# S3_LED_MAT_FPGA.net
KiCad netlist of a schematic drawn in Altium Designer
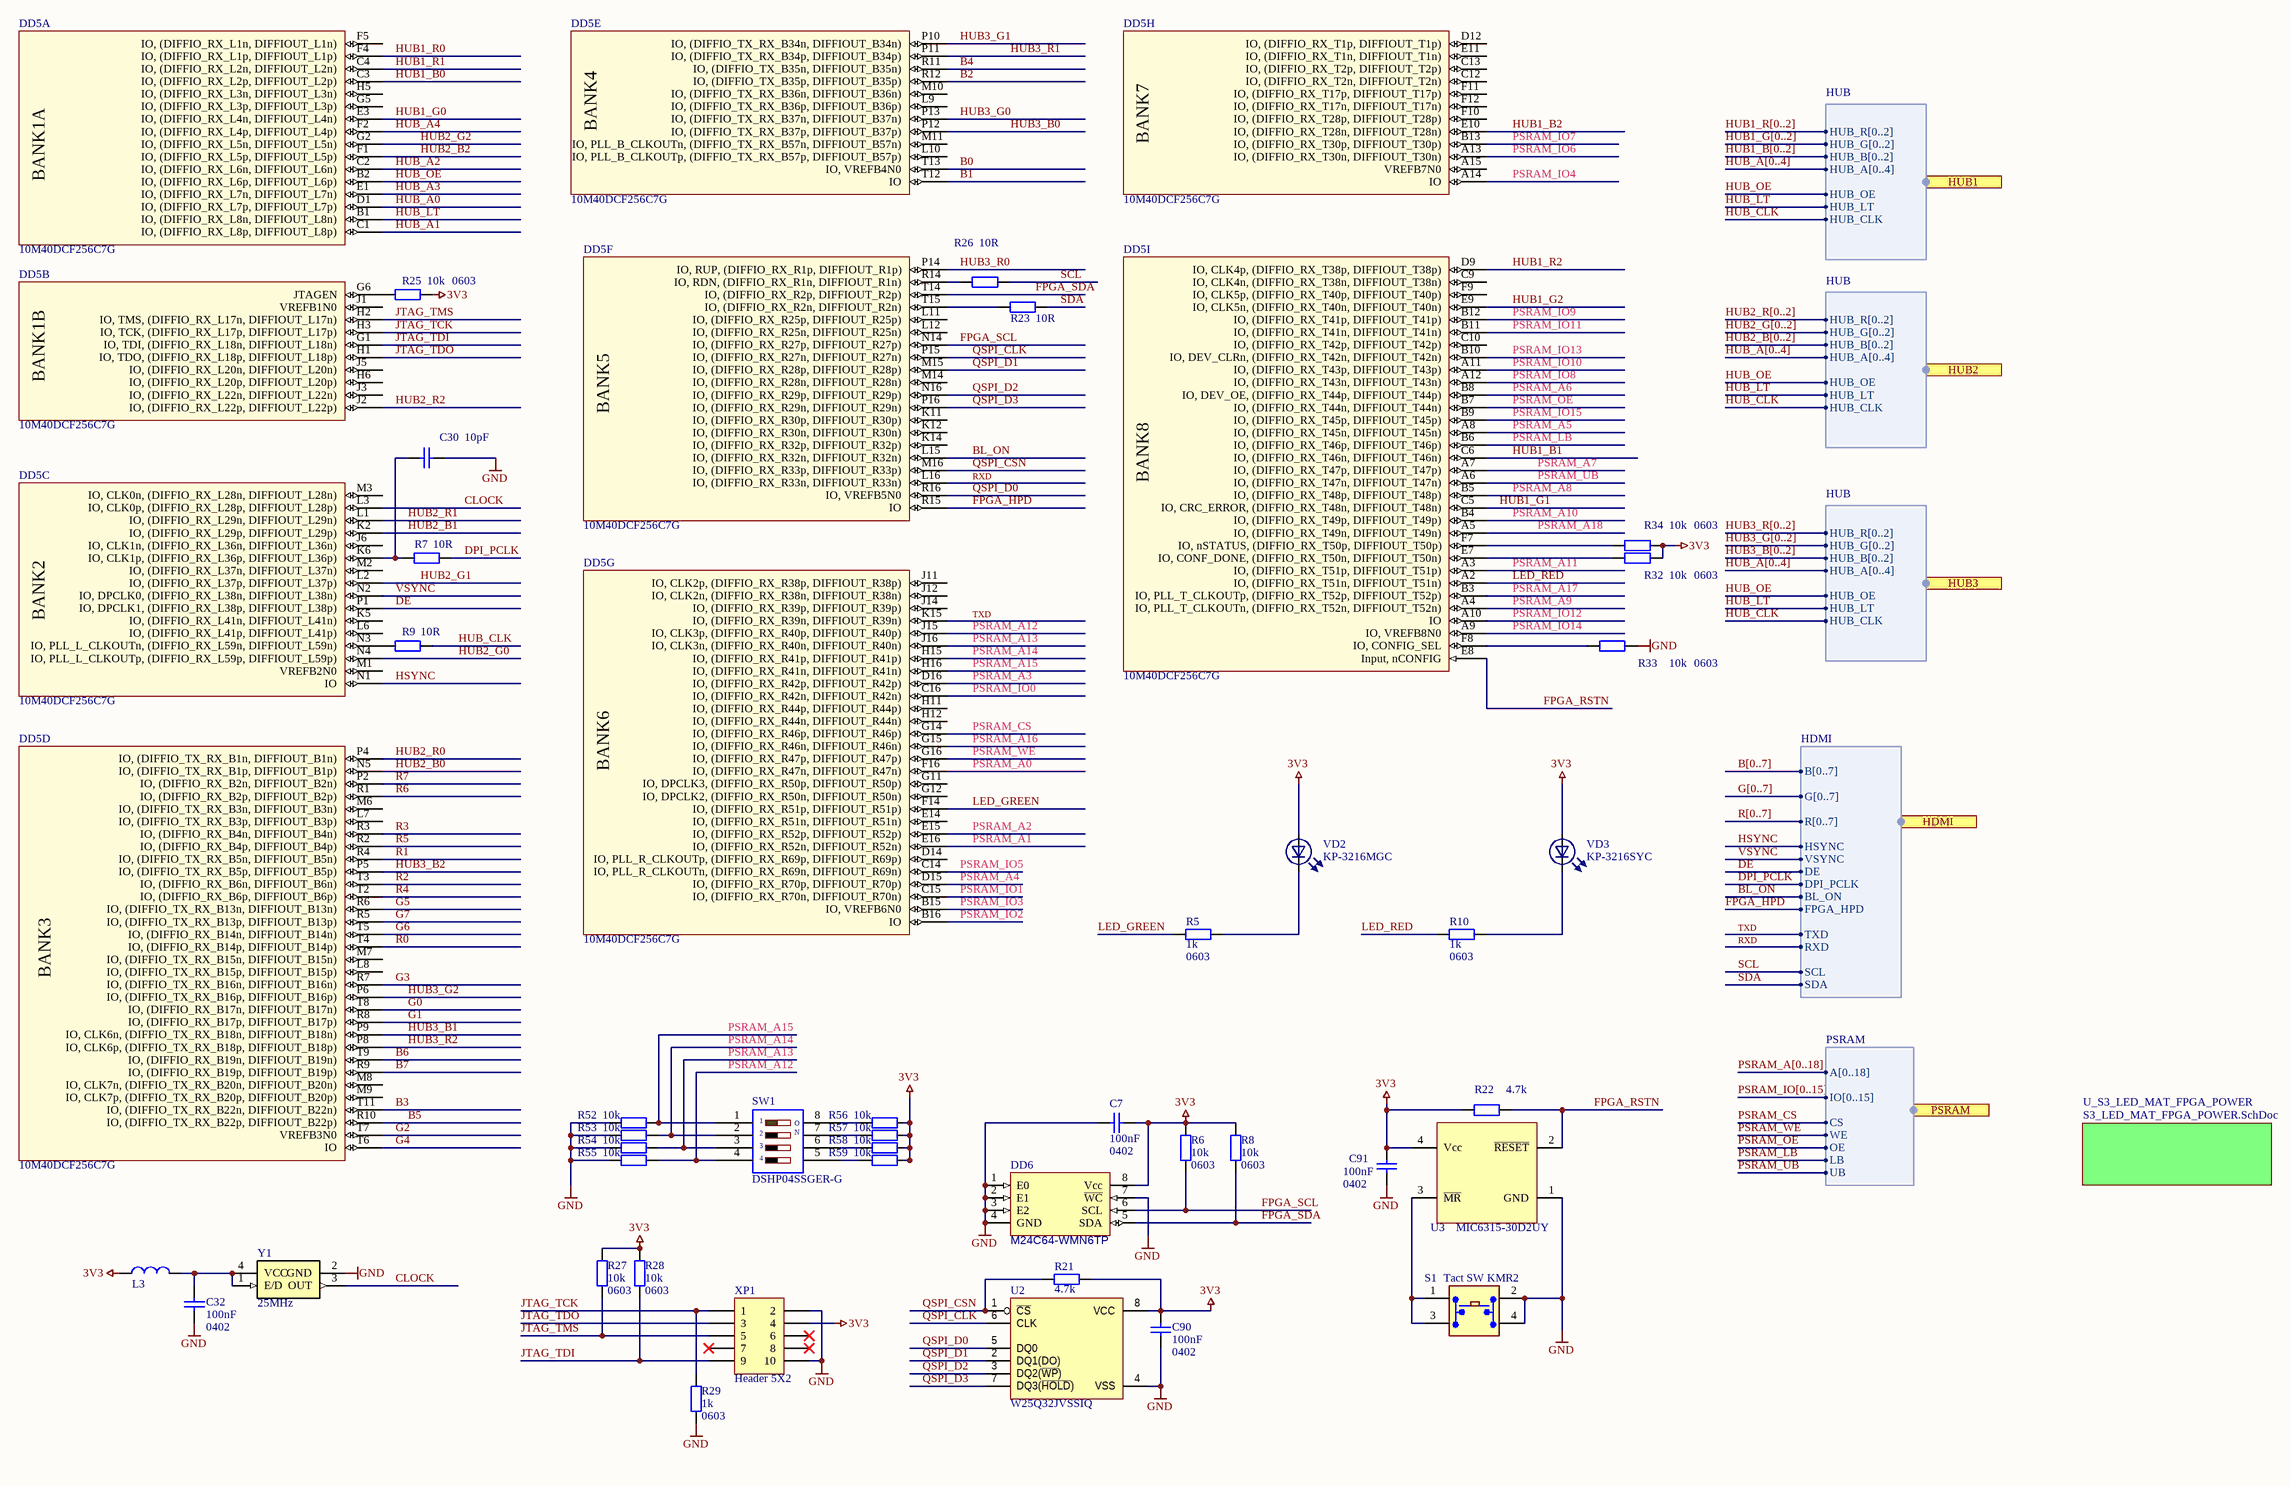
[diagram p0: S3_LED_MAT_FPGA.SCHDOC]

(export (version "E")
  (design (tool "Eeschema 10.0.6"))
  (components
    (comp (ref "C7")
      (value "100nF")
      (footprint "CAPC1005L")
      (description "Capacitor ceramic")
      (fields
        (field (name "MANUFACTURER") "SAMSUNG")
        (field (name "MANUFACTURER PART NUMBER") "CL05B104KO5NNNC")
        (field (name "PACKAGE") "0402")
      )
      (libsource (lib "LED_MAT_3") (part "100nF / 0402 / X7R / 16V"))
    )
    (comp (ref "C30")
      (value "10pF")
      (footprint "CAPC1608L")
      (description "Capacitor ceramic")
      (fields
        (field (name "MANUFACTURER") "SAMSUNG")
        (field (name "MANUFACTURER PART NUMBER") "CL10C100JB8NNNC")
      )
      (libsource (lib "LED_MAT_3") (part "10pF / 0603 / COG / 50V"))
    )
    (comp (ref "C32")
      (value "100nF")
      (footprint "CAPC1005L")
      (description "Capacitor ceramic")
      (fields
        (field (name "MANUFACTURER") "SAMSUNG")
        (field (name "MANUFACTURER PART NUMBER") "CL05B104KO5NNNC")
        (field (name "PACKAGE") "0402")
      )
      (libsource (lib "LED_MAT_3") (part "100nF / 0402 / X7R / 16V"))
    )
    (comp (ref "C90")
      (value "100nF")
      (footprint "CAPC1005L")
      (description "Capacitor ceramic")
      (fields
        (field (name "MANUFACTURER") "SAMSUNG")
        (field (name "MANUFACTURER PART NUMBER") "CL05B104KO5NNNC")
        (field (name "PACKAGE") "0402")
      )
      (libsource (lib "LED_MAT_3") (part "100nF / 0402 / X7R / 16V"))
    )
    (comp (ref "C91")
      (value "100nF")
      (footprint "CAPC1005L")
      (description "Capacitor ceramic")
      (fields
        (field (name "MANUFACTURER") "SAMSUNG")
        (field (name "MANUFACTURER PART NUMBER") "CL05B104KO5NNNC")
        (field (name "PACKAGE") "0402")
      )
      (libsource (lib "LED_MAT_3") (part "100nF / 0402 / X7R / 16V"))
    )
    (comp (ref "DD5")
      (value "10M40DCF256C7G")
      (footprint "BGA100P16X16-256")
      (description "FPGA")
      (fields
        (field (name "MANUFACTURER") "ALTERA")
        (field (name "MANUFACTURER PART NUMBER") "10M40DCF256C7GA")
      )
      (libsource (lib "IC") (part "10M40DCF256C7G"))
    )
    (comp (ref "DD6")
      (value "M24C64-WMN6TP")
      (footprint "SOIC127P600-8N")
      (fields
        (field (name "MANUFACTURER") "ST")
        (field (name "TOLERANCE") "./.")
        (field (name "VOLTAGE") "3.0...5.5V")
      )
      (libsource (lib "LED_MAT_3") (part "M24C64-WDW6TP"))
    )
    (comp (ref "L3")
      (value "~")
      (footprint "INDC1005L")
      (description "General 0402 - type Chip Inductor")
      (fields
        (field (name "MANUFACTURER") "Murata")
        (field (name "MANUFACTURER PART NUMBER") "BLM15AG601SN1")
      )
      (libsource (lib "LED_MAT_3") (part "L0402_BLM15"))
    )
    (comp (ref "R5")
      (value "1k")
      (footprint "RESC1608L")
      (description "Resistor")
      (fields (field (name "TOLERANCE") "1%") (field (name "PACKAGE") "0603") (field (name "VOLTAGE") "50V"))
      (libsource (lib "LED_MAT_3") (part "1k / 1% / 0603 / TC100 / 50V / 0.1W"))
    )
    (comp (ref "R6")
      (value "10k")
      (footprint "RESC1608L")
      (description "Resistor")
      (fields (field (name "TOLERANCE") "1%") (field (name "PACKAGE") "0603") (field (name "VOLTAGE") "50V"))
      (libsource (lib "") (part "10k / 1% / 0603 / TC100 / 50V / 0.1W_2"))
    )
    (comp (ref "R7")
      (value "10R")
      (footprint "RESC1608L")
      (description "10R / 1% / 0603")
      (fields
        (field (name "MANUFACTURER") "YAGEO")
        (field (name "MANUFACTURER PART NUMBER") "RC0603FR-0710RL")
      )
      (libsource (lib "LED_MAT_3") (part "10R / 1% / 0603"))
    )
    (comp (ref "R8")
      (value "10k")
      (footprint "RESC1608L")
      (description "Resistor")
      (fields (field (name "TOLERANCE") "1%") (field (name "PACKAGE") "0603") (field (name "VOLTAGE") "50V"))
      (libsource (lib "") (part "10k / 1% / 0603 / TC100 / 50V / 0.1W_1"))
    )
    (comp (ref "R9")
      (value "10R")
      (footprint "RESC1608L")
      (description "10R / 1% / 0603")
      (fields
        (field (name "MANUFACTURER") "YAGEO")
        (field (name "MANUFACTURER PART NUMBER") "RC0603FR-0710RL")
      )
      (libsource (lib "LED_MAT_3") (part "10R / 1% / 0603"))
    )
    (comp (ref "R10")
      (value "1k")
      (footprint "RESC1608L")
      (description "Resistor")
      (fields (field (name "TOLERANCE") "1%") (field (name "PACKAGE") "0603") (field (name "VOLTAGE") "50V"))
      (libsource (lib "LED_MAT_3") (part "1k / 1% / 0603 / TC100 / 50V / 0.1W"))
    )
    (comp (ref "R21")
      (value "4.7k")
      (footprint "RESC1608L")
      (description "4.7k / 1% / 0603")
      (fields
        (field (name "MANUFACTURER") "YAGEO")
        (field (name "MANUFACTURER PART NUMBER") "RC0603FR-074K7L")
      )
      (libsource (lib "LED_MAT_3") (part "4.7k / 1% / 0603"))
    )
    (comp (ref "R22")
      (value "4.7k")
      (footprint "RESC1608L")
      (description "4.7k / 1% / 0603")
      (fields
        (field (name "MANUFACTURER") "YAGEO")
        (field (name "MANUFACTURER PART NUMBER") "RC0603FR-074K7L")
      )
      (libsource (lib "LED_MAT_3") (part "4.7k / 1% / 0603"))
    )
    (comp (ref "R23")
      (value "10R")
      (footprint "RESC1608L")
      (description "10R / 1% / 0603")
      (fields
        (field (name "MANUFACTURER") "YAGEO")
        (field (name "MANUFACTURER PART NUMBER") "RC0603FR-0710RL")
      )
      (libsource (lib "LED_MAT_3") (part "10R / 1% / 0603"))
    )
    (comp (ref "R25")
      (value "10k")
      (footprint "RESC1608L")
      (description "Resistor")
      (fields (field (name "TOLERANCE") "1%") (field (name "PACKAGE") "0603") (field (name "VOLTAGE") "50V"))
      (libsource (lib "LED_MAT_3") (part "10k / 1% / 0603 / TC100 / 50V / 0.1W"))
    )
    (comp (ref "R26")
      (value "10R")
      (footprint "RESC1608L")
      (description "10R / 1% / 0603")
      (fields
        (field (name "MANUFACTURER") "YAGEO")
        (field (name "MANUFACTURER PART NUMBER") "RC0603FR-0710RL")
      )
      (libsource (lib "LED_MAT_3") (part "10R / 1% / 0603"))
    )
    (comp (ref "R27")
      (value "10k")
      (footprint "RESC1608L")
      (description "Resistor")
      (fields (field (name "TOLERANCE") "1%") (field (name "PACKAGE") "0603") (field (name "VOLTAGE") "50V"))
      (libsource (lib "") (part "10k / 1% / 0603 / TC100 / 50V / 0.1W_1"))
    )
    (comp (ref "R28")
      (value "10k")
      (footprint "RESC1608L")
      (description "Resistor")
      (fields (field (name "TOLERANCE") "1%") (field (name "PACKAGE") "0603") (field (name "VOLTAGE") "50V"))
      (libsource (lib "") (part "10k / 1% / 0603 / TC100 / 50V / 0.1W_1"))
    )
    (comp (ref "R29")
      (value "1k")
      (footprint "RESC1608L")
      (description "Resistor")
      (fields (field (name "TOLERANCE") "1%") (field (name "PACKAGE") "0603") (field (name "VOLTAGE") "50V"))
      (libsource (lib "") (part "1k / 1% / 0603 / TC100 / 50V / 0.1W_1"))
    )
    (comp (ref "R32")
      (value "10k")
      (footprint "RESC1608L")
      (description "Resistor")
      (fields (field (name "TOLERANCE") "1%") (field (name "PACKAGE") "0603") (field (name "VOLTAGE") "50V"))
      (libsource (lib "LED_MAT_3") (part "10k / 1% / 0603 / TC100 / 50V / 0.1W"))
    )
    (comp (ref "R33")
      (value "10k")
      (footprint "RESC1608L")
      (description "Resistor")
      (fields (field (name "TOLERANCE") "1%") (field (name "PACKAGE") "0603") (field (name "VOLTAGE") "50V"))
      (libsource (lib "LED_MAT_3") (part "10k / 1% / 0603 / TC100 / 50V / 0.1W"))
    )
    (comp (ref "R34")
      (value "10k")
      (footprint "RESC1608L")
      (description "Resistor")
      (fields (field (name "TOLERANCE") "1%") (field (name "PACKAGE") "0603") (field (name "VOLTAGE") "50V"))
      (libsource (lib "LED_MAT_3") (part "10k / 1% / 0603 / TC100 / 50V / 0.1W"))
    )
    (comp (ref "R52")
      (value "10k")
      (footprint "RESC1608L")
      (description "Resistor")
      (fields (field (name "TOLERANCE") "1%") (field (name "VOLTAGE") "50V"))
      (libsource (lib "LED_MAT_3") (part "10k / 1% / 0603 / TC100 / 50V / 0.1W"))
    )
    (comp (ref "R53")
      (value "10k")
      (footprint "RESC1608L")
      (description "Resistor")
      (fields (field (name "TOLERANCE") "1%") (field (name "VOLTAGE") "50V"))
      (libsource (lib "LED_MAT_3") (part "10k / 1% / 0603 / TC100 / 50V / 0.1W"))
    )
    (comp (ref "R54")
      (value "10k")
      (footprint "RESC1608L")
      (description "Resistor")
      (fields (field (name "TOLERANCE") "1%") (field (name "VOLTAGE") "50V"))
      (libsource (lib "LED_MAT_3") (part "10k / 1% / 0603 / TC100 / 50V / 0.1W"))
    )
    (comp (ref "R55")
      (value "10k")
      (footprint "RESC1608L")
      (description "Resistor")
      (fields (field (name "TOLERANCE") "1%") (field (name "VOLTAGE") "50V"))
      (libsource (lib "LED_MAT_3") (part "10k / 1% / 0603 / TC100 / 50V / 0.1W"))
    )
    (comp (ref "R56")
      (value "10k")
      (footprint "RESC1608L")
      (description "Resistor")
      (fields (field (name "TOLERANCE") "1%") (field (name "VOLTAGE") "50V"))
      (libsource (lib "LED_MAT_3") (part "10k / 1% / 0603 / TC100 / 50V / 0.1W"))
    )
    (comp (ref "R57")
      (value "10k")
      (footprint "RESC1608L")
      (description "Resistor")
      (fields (field (name "TOLERANCE") "1%") (field (name "VOLTAGE") "50V"))
      (libsource (lib "LED_MAT_3") (part "10k / 1% / 0603 / TC100 / 50V / 0.1W"))
    )
    (comp (ref "R58")
      (value "10k")
      (footprint "RESC1608L")
      (description "Resistor")
      (fields (field (name "TOLERANCE") "1%") (field (name "VOLTAGE") "50V"))
      (libsource (lib "LED_MAT_3") (part "10k / 1% / 0603 / TC100 / 50V / 0.1W"))
    )
    (comp (ref "R59")
      (value "10k")
      (footprint "RESC1608L")
      (description "Resistor")
      (fields (field (name "TOLERANCE") "1%") (field (name "VOLTAGE") "50V"))
      (libsource (lib "LED_MAT_3") (part "10k / 1% / 0603 / TC100 / 50V / 0.1W"))
    )
    (comp (ref "S1")
      (value "Tact SW KMR2")
      (footprint "SW4SMD_63X161LS")
      (description "Microminiature Tact Switch for SMT")
      (fields
        (field (name "MANUFACTURER") "C&K Components")
        (field (name "MANUFACTURER PART NUMBER") "KMR211GLFS")
      )
      (libsource (lib "LED_MAT_3") (part "Tact SW KMR2"))
    )
    (comp (ref "SW1")
      (value "DSHP04SSGER-G")
      (footprint "Dipswitch 4 SO8 a")
      (description "DIP SW 4pol, 1.27mm")
      (fields (field (name "MANUFACTURER") "SWITRONIC") (field (name "TOLERANCE") "1%"))
      (libsource (lib "LED_MAT_3") (part "DIP SW 4pol, 1.27mm"))
    )
    (comp (ref "U2")
      (value "W25Q32JVSSIQ")
      (footprint "SOIC127P800X216-8L")
      (description "32Mbit Quad Serial Flash in SOIC W package")
      (fields (field (name "MANUFACTURER") "WINBOND") (field (name "TOLERANCE") "./."))
      (libsource (lib "LED_MAT_3") (part "W25Q32JVSSIQ"))
    )
    (comp (ref "U3")
      (value "MIC6315-30D2UY")
      (footprint "SOT-143")
      (description "3V VOLTAGE SUPERVISOR")
      (fields (field (name "MANUFACTURER") "MICROCHIP") (field (name "VOLTAGE") "3.3V"))
      (libsource (lib "LED_MAT_3") (part "MIC6315"))
    )
    (comp (ref "VD2")
      (value "KP-3216MGC")
      (footprint "LED3216X10L")
      (description "SMD LED GREEN")
      (fields (field (name "MANUFACTURER") "KINGBRIGHT"))
      (libsource (lib "LED_MAT_3") (part "KP-3216MGC"))
    )
    (comp (ref "VD3")
      (value "KP-3216SYC")
      (footprint "LED3216X10L")
      (description "SMD LED YELLOW")
      (fields (field (name "MANUFACTURER") "KINGBRIGHT"))
      (libsource (lib "LED_MAT_3") (part "KP-3216SYC"))
    )
    (comp (ref "XP1")
      (value "Header 5X2")
      (footprint "PLD10")
      (description "Header, 5-Pin, Dual row")
      (fields (field (name "MANUFACTURER") "FCI") (field (name "VOLTAGE") "50V"))
      (libsource (lib "LED_MAT_3") (part "Header 5X2"))
    )
    (comp (ref "Y1")
      (value "25MHz")
      (footprint "SMD03025/4CC")
      (description "SMD Oscillator with Stop Function")
      (fields
        (field (name "MANUFACTURER") "YOKETANT")
        (field (name "MANUFACTURER PART NUMBER") "SO3225-025000-FIE-BBA-A1")
      )
      (libsource (lib "LED_MAT_3") (part "OSC / 3225 / 25M"))
    )
  )
  (nets
    (net (code "6") (name "/B0") (class "Default")
      (node (ref "DD5") (pin "T13") (pinfunction "IO,_VREFB4N0_T13") (pintype "bidirectional"))
    )
    (net (code "7") (name "/B1") (class "Default")
      (node (ref "DD5") (pin "T12") (pinfunction "IO_T12") (pintype "bidirectional"))
    )
    (net (code "8") (name "/B2") (class "Default")
      (node (ref "DD5") (pin "R12") (pinfunction "IO,_(DIFFIO_TX_B35p,_DIFFIOUT_B35p)_R12") (pintype "bidirectional"))
    )
    (net (code "9") (name "/B3") (class "Default")
      (node (ref "DD5") (pin "T11") (pinfunction "IO,_(DIFFIO_TX_RX_B22n,_DIFFIOUT_B22n)_T11") (pintype "bidirectional"))
    )
    (net (code "10") (name "/B4") (class "Default")
      (node (ref "DD5") (pin "R11") (pinfunction "IO,_(DIFFIO_TX_B35n,_DIFFIOUT_B35n)_R11") (pintype "bidirectional"))
    )
    (net (code "11") (name "/B5") (class "Default")
      (node (ref "DD5") (pin "R10") (pinfunction "IO,_(DIFFIO_TX_RX_B22p,_DIFFIOUT_B22p)_R10") (pintype "bidirectional"))
    )
    (net (code "12") (name "/B6") (class "Default")
      (node (ref "DD5") (pin "T9") (pinfunction "IO,_(DIFFIO_RX_B19n,_DIFFIOUT_B19n)_T9") (pintype "bidirectional"))
    )
    (net (code "13") (name "/B7") (class "Default")
      (node (ref "DD5") (pin "R9") (pinfunction "IO,_(DIFFIO_RX_B19p,_DIFFIOUT_B19p)_R9") (pintype "bidirectional"))
    )
    (net (code "14") (name "/BL_ON") (class "Default")
      (node (ref "DD5") (pin "L15") (pinfunction "IO,_(DIFFIO_RX_R32n,_DIFFIOUT_R32n)_L15") (pintype "bidirectional"))
    )
    (net (code "16") (name "/CLOCK") (class "Default")
      (node (ref "DD5") (pin "L3") (pinfunction "IO,_CLK0p,_(DIFFIO_RX_L28p,_DIFFIOUT_L28p)_L3") (pintype "bidirectional"))
      (node (ref "Y1") (pin "3") (pinfunction "OUT_3") (pintype "output"))
    )
    (net (code "17") (name "/DE") (class "Default")
      (node (ref "DD5") (pin "P1") (pinfunction "IO,_DPCLK1,_(DIFFIO_RX_L38p,_DIFFIOUT_L38p)_P1") (pintype "bidirectional"))
    )
    (net (code "18") (name "/DPI_PCLK") (class "Default")
      (node (ref "R7") (pin "1") (pinfunction "1_1") (pintype "passive"))
    )
    (net (code "19") (name "/FPGA_HPD") (class "Default")
      (node (ref "DD5") (pin "R15") (pinfunction "IO_R15") (pintype "bidirectional"))
    )
    (net (code "20") (name "/FPGA_RSTN") (class "Default")
      (node (ref "DD5") (pin "E8") (pinfunction "Input,_nCONFIG_E8") (pintype "input"))
      (node (ref "R22") (pin "2") (pinfunction "2_2") (pintype "passive"))
      (node (ref "U3") (pin "2") (pinfunction "~{RESET}_2") (pintype "passive"))
    )
    (net (code "21") (name "/FPGA_SCL") (class "Default")
      (node (ref "DD5") (pin "N14") (pinfunction "IO,_(DIFFIO_RX_R27p,_DIFFIOUT_R27p)_N14") (pintype "bidirectional"))
      (node (ref "DD6") (pin "6") (pinfunction "SCL_6") (pintype "input"))
      (node (ref "R6") (pin "1") (pinfunction "1_1") (pintype "passive"))
    )
    (net (code "22") (name "/FPGA_SDA") (class "Default")
      (node (ref "DD5") (pin "T14") (pinfunction "IO,_(DIFFIO_RX_R2p,_DIFFIOUT_R2p)_T14") (pintype "bidirectional"))
      (node (ref "DD6") (pin "5") (pinfunction "SDA_5") (pintype "bidirectional"))
      (node (ref "R8") (pin "2") (pinfunction "2_2") (pintype "passive"))
    )
    (net (code "23") (name "/G0") (class "Default")
      (node (ref "DD5") (pin "T8") (pinfunction "IO,_(DIFFIO_RX_B17n,_DIFFIOUT_B17n)_T8") (pintype "bidirectional"))
    )
    (net (code "24") (name "/G1") (class "Default")
      (node (ref "DD5") (pin "R8") (pinfunction "IO,_(DIFFIO_RX_B17p,_DIFFIOUT_B17p)_R8") (pintype "bidirectional"))
    )
    (net (code "25") (name "/G2") (class "Default")
      (node (ref "DD5") (pin "T7") (pinfunction "VREFB3N0_T7") (pintype "bidirectional"))
    )
    (net (code "26") (name "/G3") (class "Default")
      (node (ref "DD5") (pin "R7") (pinfunction "IO,_(DIFFIO_TX_RX_B16n,_DIFFIOUT_B16n)_R7") (pintype "bidirectional"))
    )
    (net (code "27") (name "/G4") (class "Default")
      (node (ref "DD5") (pin "T6") (pinfunction "IO_T6") (pintype "bidirectional"))
    )
    (net (code "28") (name "/G5") (class "Default")
      (node (ref "DD5") (pin "R6") (pinfunction "IO,_(DIFFIO_TX_RX_B13n,_DIFFIOUT_B13n)_R6") (pintype "bidirectional"))
    )
    (net (code "29") (name "/G6") (class "Default")
      (node (ref "DD5") (pin "T5") (pinfunction "IO,_(DIFFIO_RX_B14n,_DIFFIOUT_B14n)_T5") (pintype "bidirectional"))
    )
    (net (code "30") (name "/G7") (class "Default")
      (node (ref "DD5") (pin "R5") (pinfunction "IO,_(DIFFIO_TX_RX_B13p,_DIFFIOUT_B13p)_R5") (pintype "bidirectional"))
    )
    (net (code "33") (name "/HSYNC") (class "Default")
      (node (ref "DD5") (pin "N1") (pinfunction "IO_N1") (pintype "bidirectional"))
    )
    (net (code "34") (name "/HUB1_B0") (class "Default")
      (node (ref "DD5") (pin "C3") (pinfunction "IO,_(DIFFIO_RX_L2p,_DIFFIOUT_L2p)_C3") (pintype "bidirectional"))
    )
    (net (code "35") (name "/HUB1_B1") (class "Default")
      (node (ref "DD5") (pin "C6") (pinfunction "IO,_(DIFFIO_RX_T46n,_DIFFIOUT_T46n)_C6") (pintype "bidirectional"))
    )
    (net (code "36") (name "/HUB1_B2") (class "Default")
      (node (ref "DD5") (pin "E10") (pinfunction "IO,_(DIFFIO_RX_T28n,_DIFFIOUT_T28n)_E10") (pintype "bidirectional"))
    )
    (net (code "38") (name "/HUB1_G0") (class "Default")
      (node (ref "DD5") (pin "E3") (pinfunction "IO,_(DIFFIO_RX_L4n,_DIFFIOUT_L4n)_E3") (pintype "bidirectional"))
    )
    (net (code "39") (name "/HUB1_G1") (class "Default")
      (node (ref "DD5") (pin "C5") (pinfunction "IO,_CRC_ERROR,_(DIFFIO_RX_T48n,_DIFFIOUT_T48n)_C5") (pintype "bidirectional"))
    )
    (net (code "40") (name "/HUB1_G2") (class "Default")
      (node (ref "DD5") (pin "E9") (pinfunction "IO,_CLK5n,_(DIFFIO_RX_T40n,_DIFFIOUT_T40n)_E9") (pintype "bidirectional"))
    )
    (net (code "42") (name "/HUB1_R0") (class "Default")
      (node (ref "DD5") (pin "F4") (pinfunction "IO,_(DIFFIO_RX_L1p,_DIFFIOUT_L1p)_F4") (pintype "bidirectional"))
    )
    (net (code "43") (name "/HUB1_R1") (class "Default")
      (node (ref "DD5") (pin "C4") (pinfunction "IO,_(DIFFIO_RX_L2n,_DIFFIOUT_L2n)_C4") (pintype "bidirectional"))
    )
    (net (code "44") (name "/HUB1_R2") (class "Default")
      (node (ref "DD5") (pin "D9") (pinfunction "IO,_CLK4p,_(DIFFIO_RX_T38p,_DIFFIOUT_T38p)_D9") (pintype "bidirectional"))
    )
    (net (code "47") (name "/HUB2_B0") (class "Default")
      (node (ref "DD5") (pin "N5") (pinfunction "IO,_(DIFFIO_TX_RX_B1p,_DIFFIOUT_B1p)_N5") (pintype "bidirectional"))
    )
    (net (code "48") (name "/HUB2_B1") (class "Default")
      (node (ref "DD5") (pin "K2") (pinfunction "IO,_(DIFFIO_RX_L29p,_DIFFIOUT_L29p)_K2") (pintype "bidirectional"))
    )
    (net (code "49") (name "/HUB2_B2") (class "Default")
      (node (ref "DD5") (pin "F1") (pinfunction "IO,_(DIFFIO_RX_L5p,_DIFFIOUT_L5p)_F1") (pintype "bidirectional"))
    )
    (net (code "50") (name "/HUB2_G0") (class "Default")
      (node (ref "DD5") (pin "N4") (pinfunction "IO,_PLL_L_CLKOUTp,_(DIFFIO_RX_L59p,_DIFFIOUT_L59p)_N4") (pintype "bidirectional"))
    )
    (net (code "51") (name "/HUB2_G1") (class "Default")
      (node (ref "DD5") (pin "L2") (pinfunction "IO,_(DIFFIO_RX_L37p,_DIFFIOUT_L37p)_L2") (pintype "bidirectional"))
    )
    (net (code "52") (name "/HUB2_G2") (class "Default")
      (node (ref "DD5") (pin "G2") (pinfunction "IO,_(DIFFIO_RX_L5n,_DIFFIOUT_L5n)_G2") (pintype "bidirectional"))
    )
    (net (code "54") (name "/HUB2_R0") (class "Default")
      (node (ref "DD5") (pin "P4") (pinfunction "IO,_(DIFFIO_TX_RX_B1n,_DIFFIOUT_B1n)_P4") (pintype "bidirectional"))
    )
    (net (code "55") (name "/HUB2_R1") (class "Default")
      (node (ref "DD5") (pin "L1") (pinfunction "IO,_(DIFFIO_RX_L29n,_DIFFIOUT_L29n)_L1") (pintype "bidirectional"))
    )
    (net (code "56") (name "/HUB2_R2") (class "Default")
      (node (ref "DD5") (pin "J2") (pinfunction "IO,_(DIFFIO_RX_L22p,_DIFFIOUT_L22p)_J2") (pintype "bidirectional"))
    )
    (net (code "59") (name "/HUB3_B0") (class "Default")
      (node (ref "DD5") (pin "P12") (pinfunction "IO,_(DIFFIO_TX_RX_B37p,_DIFFIOUT_B37p)_P12") (pintype "bidirectional"))
    )
    (net (code "60") (name "/HUB3_B1") (class "Default")
      (node (ref "DD5") (pin "P9") (pinfunction "IO,_CLK6n,_(DIFFIO_TX_RX_B18n,_DIFFIOUT_B18n)_P9") (pintype "bidirectional"))
    )
    (net (code "61") (name "/HUB3_B2") (class "Default")
      (node (ref "DD5") (pin "P5") (pinfunction "IO,_(DIFFIO_TX_RX_B5p,_DIFFIOUT_B5p)_P5") (pintype "bidirectional"))
    )
    (net (code "63") (name "/HUB3_G0") (class "Default")
      (node (ref "DD5") (pin "P13") (pinfunction "IO,_(DIFFIO_TX_RX_B37n,_DIFFIOUT_B37n)_P13") (pintype "bidirectional"))
    )
    (net (code "64") (name "/HUB3_G1") (class "Default")
      (node (ref "DD5") (pin "P10") (pinfunction "IO,_(DIFFIO_TX_RX_B34n,_DIFFIOUT_B34n)_P10") (pintype "bidirectional"))
    )
    (net (code "65") (name "/HUB3_G2") (class "Default")
      (node (ref "DD5") (pin "P6") (pinfunction "IO,_(DIFFIO_TX_RX_B16p,_DIFFIOUT_B16p)_P6") (pintype "bidirectional"))
    )
    (net (code "67") (name "/HUB3_R0") (class "Default")
      (node (ref "DD5") (pin "P14") (pinfunction "IO,_RUP,_(DIFFIO_RX_R1p,_DIFFIOUT_R1p)_P14") (pintype "bidirectional"))
    )
    (net (code "68") (name "/HUB3_R1") (class "Default")
      (node (ref "DD5") (pin "P11") (pinfunction "IO,_(DIFFIO_TX_RX_B34p,_DIFFIOUT_B34p)_P11") (pintype "bidirectional"))
    )
    (net (code "69") (name "/HUB3_R2") (class "Default")
      (node (ref "DD5") (pin "P8") (pinfunction "IO,_CLK6p,_(DIFFIO_TX_RX_B18p,_DIFFIOUT_B18p)_P8") (pintype "bidirectional"))
    )
    (net (code "72") (name "/HUB_A0") (class "Default")
      (node (ref "DD5") (pin "D1") (pinfunction "IO,_(DIFFIO_RX_L7p,_DIFFIOUT_L7p)_D1") (pintype "bidirectional"))
    )
    (net (code "73") (name "/HUB_A1") (class "Default")
      (node (ref "DD5") (pin "C1") (pinfunction "IO,_(DIFFIO_RX_L8p,_DIFFIOUT_L8p)_C1") (pintype "bidirectional"))
    )
    (net (code "74") (name "/HUB_A2") (class "Default")
      (node (ref "DD5") (pin "C2") (pinfunction "IO,_(DIFFIO_RX_L6n,_DIFFIOUT_L6n)_C2") (pintype "bidirectional"))
    )
    (net (code "75") (name "/HUB_A3") (class "Default")
      (node (ref "DD5") (pin "E1") (pinfunction "IO,_(DIFFIO_RX_L7n,_DIFFIOUT_L7n)_E1") (pintype "bidirectional"))
    )
    (net (code "76") (name "/HUB_A4") (class "Default")
      (node (ref "DD5") (pin "F2") (pinfunction "IO,_(DIFFIO_RX_L4p,_DIFFIOUT_L4p)_F2") (pintype "bidirectional"))
    )
    (net (code "78") (name "/HUB_CLK") (class "Default")
      (node (ref "R9") (pin "1") (pinfunction "1_1") (pintype "passive"))
    )
    (net (code "79") (name "/HUB_LT") (class "Default")
      (node (ref "DD5") (pin "B1") (pinfunction "IO,_(DIFFIO_RX_L8n,_DIFFIOUT_L8n)_B1") (pintype "bidirectional"))
    )
    (net (code "80") (name "/HUB_OE") (class "Default")
      (node (ref "DD5") (pin "B2") (pinfunction "IO,_(DIFFIO_RX_L6p,_DIFFIOUT_L6p)_B2") (pintype "bidirectional"))
    )
    (net (code "81") (name "/JTAG_TCK") (class "Default")
      (node (ref "DD5") (pin "H3") (pinfunction "IO,_TCK,_(DIFFIO_RX_L17p,_DIFFIOUT_L17p)_H3") (pintype "bidirectional"))
      (node (ref "R29") (pin "1") (pinfunction "1_1") (pintype "passive"))
      (node (ref "XP1") (pin "1") (pinfunction "1_1") (pintype "passive"))
    )
    (net (code "82") (name "/JTAG_TDI") (class "Default")
      (node (ref "DD5") (pin "G1") (pinfunction "IO,_TDI,_(DIFFIO_RX_L18n,_DIFFIOUT_L18n)_G1") (pintype "bidirectional"))
      (node (ref "R28") (pin "2") (pinfunction "2_2") (pintype "passive"))
      (node (ref "XP1") (pin "9") (pinfunction "9_9") (pintype "passive"))
    )
    (net (code "83") (name "/JTAG_TDO") (class "Default")
      (node (ref "DD5") (pin "H1") (pinfunction "IO,_TDO,_(DIFFIO_RX_L18p,_DIFFIOUT_L18p)_H1") (pintype "bidirectional"))
      (node (ref "XP1") (pin "3") (pinfunction "3_3") (pintype "passive"))
    )
    (net (code "84") (name "/JTAG_TMS") (class "Default")
      (node (ref "DD5") (pin "H2") (pinfunction "IO,_TMS,_(DIFFIO_RX_L17n,_DIFFIOUT_L17n)_H2") (pintype "bidirectional"))
      (node (ref "R27") (pin "2") (pinfunction "2_2") (pintype "passive"))
      (node (ref "XP1") (pin "5") (pinfunction "5_5") (pintype "passive"))
    )
    (net (code "85") (name "/LED_GREEN") (class "Default")
      (node (ref "DD5") (pin "F14") (pinfunction "IO,_(DIFFIO_RX_R51p,_DIFFIOUT_R51p)_F14") (pintype "bidirectional"))
      (node (ref "R5") (pin "2") (pinfunction "2_2") (pintype "passive"))
    )
    (net (code "86") (name "/LED_RED") (class "Default")
      (node (ref "DD5") (pin "A2") (pinfunction "IO,_(DIFFIO_RX_T51n,_DIFFIOUT_T51n)_A2") (pintype "bidirectional"))
      (node (ref "R10") (pin "2") (pinfunction "2_2") (pintype "passive"))
    )
    (net (code "87") (name "/PSRAM_A0") (class "Default")
      (node (ref "DD5") (pin "F16") (pinfunction "IO,_(DIFFIO_RX_R47n,_DIFFIOUT_R47n)_F16") (pintype "bidirectional"))
    )
    (net (code "88") (name "/PSRAM_A1") (class "Default")
      (node (ref "DD5") (pin "E16") (pinfunction "IO,_(DIFFIO_RX_R52n,_DIFFIOUT_R52n)_E16") (pintype "bidirectional"))
    )
    (net (code "89") (name "/PSRAM_A2") (class "Default")
      (node (ref "DD5") (pin "E15") (pinfunction "IO,_(DIFFIO_RX_R52p,_DIFFIOUT_R52p)_E15") (pintype "bidirectional"))
    )
    (net (code "90") (name "/PSRAM_A3") (class "Default")
      (node (ref "DD5") (pin "D16") (pinfunction "IO,_(DIFFIO_RX_R42p,_DIFFIOUT_R42p)_D16") (pintype "bidirectional"))
    )
    (net (code "91") (name "/PSRAM_A4") (class "Default")
      (node (ref "DD5") (pin "D15") (pinfunction "IO,_(DIFFIO_RX_R70p,_DIFFIOUT_R70p)_D15") (pintype "bidirectional"))
    )
    (net (code "92") (name "/PSRAM_A5") (class "Default")
      (node (ref "DD5") (pin "A8") (pinfunction "IO,_(DIFFIO_RX_T45n,_DIFFIOUT_T45n)_A8") (pintype "bidirectional"))
    )
    (net (code "93") (name "/PSRAM_A6") (class "Default")
      (node (ref "DD5") (pin "B8") (pinfunction "IO,_DEV_OE,_(DIFFIO_RX_T44p,_DIFFIOUT_T44p)_B8") (pintype "bidirectional"))
    )
    (net (code "94") (name "/PSRAM_A7") (class "Default")
      (node (ref "DD5") (pin "A7") (pinfunction "IO,_(DIFFIO_RX_T47p,_DIFFIOUT_T47p)_A7") (pintype "bidirectional"))
    )
    (net (code "95") (name "/PSRAM_A8") (class "Default")
      (node (ref "DD5") (pin "B5") (pinfunction "IO,_(DIFFIO_RX_T48p,_DIFFIOUT_T48p)_B5") (pintype "bidirectional"))
    )
    (net (code "96") (name "/PSRAM_A9") (class "Default")
      (node (ref "DD5") (pin "A4") (pinfunction "IO,_PLL_T_CLKOUTn,_(DIFFIO_RX_T52n,_DIFFIOUT_T52n)_A4") (pintype "bidirectional"))
    )
    (net (code "97") (name "/PSRAM_A10") (class "Default")
      (node (ref "DD5") (pin "B4") (pinfunction "IO,_(DIFFIO_RX_T49p,_DIFFIOUT_T49p)_B4") (pintype "bidirectional"))
    )
    (net (code "98") (name "/PSRAM_A11") (class "Default")
      (node (ref "DD5") (pin "A3") (pinfunction "IO,_(DIFFIO_RX_T51p,_DIFFIOUT_T51p)_A3") (pintype "bidirectional"))
    )
    (net (code "99") (name "/PSRAM_A12") (class "Default")
      (node (ref "DD5") (pin "J15") (pinfunction "IO,_CLK3p,_(DIFFIO_RX_R40p,_DIFFIOUT_R40p)_J15") (pintype "bidirectional"))
      (node (ref "R55") (pin "1") (pinfunction "1_1") (pintype "passive"))
      (node (ref "SW1") (pin "4") (pintype "passive"))
    )
    (net (code "100") (name "/PSRAM_A13") (class "Default")
      (node (ref "DD5") (pin "J16") (pinfunction "IO,_CLK3n,_(DIFFIO_RX_R40n,_DIFFIOUT_R40n)_J16") (pintype "bidirectional"))
      (node (ref "R54") (pin "1") (pinfunction "1_1") (pintype "passive"))
      (node (ref "SW1") (pin "3") (pintype "passive"))
    )
    (net (code "101") (name "/PSRAM_A14") (class "Default")
      (node (ref "DD5") (pin "H15") (pinfunction "IO,_(DIFFIO_RX_R41p,_DIFFIOUT_R41p)_H15") (pintype "bidirectional"))
      (node (ref "R53") (pin "1") (pinfunction "1_1") (pintype "passive"))
      (node (ref "SW1") (pin "2") (pintype "passive"))
    )
    (net (code "102") (name "/PSRAM_A15") (class "Default")
      (node (ref "DD5") (pin "H16") (pinfunction "IO,_(DIFFIO_RX_R41n,_DIFFIOUT_R41n)_H16") (pintype "bidirectional"))
      (node (ref "R52") (pin "1") (pinfunction "1_1") (pintype "passive"))
      (node (ref "SW1") (pin "1") (pintype "passive"))
    )
    (net (code "103") (name "/PSRAM_A16") (class "Default")
      (node (ref "DD5") (pin "G15") (pinfunction "IO,_(DIFFIO_RX_R46n,_DIFFIOUT_R46n)_G15") (pintype "bidirectional"))
    )
    (net (code "104") (name "/PSRAM_A17") (class "Default")
      (node (ref "DD5") (pin "B3") (pinfunction "IO,_PLL_T_CLKOUTp,_(DIFFIO_RX_T52p,_DIFFIOUT_T52p)_B3") (pintype "bidirectional"))
    )
    (net (code "105") (name "/PSRAM_A18") (class "Default")
      (node (ref "DD5") (pin "A5") (pinfunction "IO,_(DIFFIO_RX_T49n,_DIFFIOUT_T49n)_A5") (pintype "bidirectional"))
    )
    (net (code "107") (name "/PSRAM_CS") (class "Default")
      (node (ref "DD5") (pin "G14") (pinfunction "IO,_(DIFFIO_RX_R46p,_DIFFIOUT_R46p)_G14") (pintype "bidirectional"))
    )
    (net (code "108") (name "/PSRAM_IO0") (class "Default")
      (node (ref "DD5") (pin "C16") (pinfunction "IO,_(DIFFIO_RX_R42n,_DIFFIOUT_R42n)_C16") (pintype "bidirectional"))
    )
    (net (code "109") (name "/PSRAM_IO1") (class "Default")
      (node (ref "DD5") (pin "C15") (pinfunction "IO,_(DIFFIO_RX_R70n,_DIFFIOUT_R70n)_C15") (pintype "bidirectional"))
    )
    (net (code "110") (name "/PSRAM_IO2") (class "Default")
      (node (ref "DD5") (pin "B16") (pinfunction "IO_B16") (pintype "bidirectional"))
    )
    (net (code "111") (name "/PSRAM_IO3") (class "Default")
      (node (ref "DD5") (pin "B15") (pinfunction "IO,_VREFB6N0_B15") (pintype "bidirectional"))
    )
    (net (code "112") (name "/PSRAM_IO4") (class "Default")
      (node (ref "DD5") (pin "A14") (pinfunction "IO_A14") (pintype "bidirectional"))
    )
    (net (code "113") (name "/PSRAM_IO5") (class "Default")
      (node (ref "DD5") (pin "C14") (pinfunction "IO,_PLL_R_CLKOUTn,_(DIFFIO_RX_R69n,_DIFFIOUT_R69n)_C14") (pintype "bidirectional"))
    )
    (net (code "114") (name "/PSRAM_IO6") (class "Default")
      (node (ref "DD5") (pin "A13") (pinfunction "IO,_(DIFFIO_RX_T30n,_DIFFIOUT_T30n)_A13") (pintype "bidirectional"))
    )
    (net (code "115") (name "/PSRAM_IO7") (class "Default")
      (node (ref "DD5") (pin "B13") (pinfunction "IO,_(DIFFIO_RX_T30p,_DIFFIOUT_T30p)_B13") (pintype "bidirectional"))
    )
    (net (code "116") (name "/PSRAM_IO8") (class "Default")
      (node (ref "DD5") (pin "A12") (pinfunction "IO,_(DIFFIO_RX_T43n,_DIFFIOUT_T43n)_A12") (pintype "bidirectional"))
    )
    (net (code "117") (name "/PSRAM_IO9") (class "Default")
      (node (ref "DD5") (pin "B12") (pinfunction "IO,_(DIFFIO_RX_T41p,_DIFFIOUT_T41p)_B12") (pintype "bidirectional"))
    )
    (net (code "118") (name "/PSRAM_IO10") (class "Default")
      (node (ref "DD5") (pin "A11") (pinfunction "IO,_(DIFFIO_RX_T43p,_DIFFIOUT_T43p)_A11") (pintype "bidirectional"))
    )
    (net (code "119") (name "/PSRAM_IO11") (class "Default")
      (node (ref "DD5") (pin "B11") (pinfunction "IO,_(DIFFIO_RX_T41n,_DIFFIOUT_T41n)_B11") (pintype "bidirectional"))
    )
    (net (code "120") (name "/PSRAM_IO12") (class "Default")
      (node (ref "DD5") (pin "A10") (pinfunction "IO_A10") (pintype "bidirectional"))
    )
    (net (code "121") (name "/PSRAM_IO13") (class "Default")
      (node (ref "DD5") (pin "B10") (pinfunction "IO,_DEV_CLRn,_(DIFFIO_RX_T42n,_DIFFIOUT_T42n)_B10") (pintype "bidirectional"))
    )
    (net (code "122") (name "/PSRAM_IO14") (class "Default")
      (node (ref "DD5") (pin "A9") (pinfunction "IO,_VREFB8N0_A9") (pintype "bidirectional"))
    )
    (net (code "123") (name "/PSRAM_IO15") (class "Default")
      (node (ref "DD5") (pin "B9") (pinfunction "IO,_(DIFFIO_RX_T45p,_DIFFIOUT_T45p)_B9") (pintype "bidirectional"))
    )
    (net (code "124") (name "/PSRAM_LB") (class "Default")
      (node (ref "DD5") (pin "B6") (pinfunction "IO,_(DIFFIO_RX_T46p,_DIFFIOUT_T46p)_B6") (pintype "bidirectional"))
    )
    (net (code "125") (name "/PSRAM_OE") (class "Default")
      (node (ref "DD5") (pin "B7") (pinfunction "IO,_(DIFFIO_RX_T44n,_DIFFIOUT_T44n)_B7") (pintype "bidirectional"))
    )
    (net (code "126") (name "/PSRAM_UB") (class "Default")
      (node (ref "DD5") (pin "A6") (pinfunction "IO,_(DIFFIO_RX_T47n,_DIFFIOUT_T47n)_A6") (pintype "bidirectional"))
    )
    (net (code "127") (name "/PSRAM_WE") (class "Default")
      (node (ref "DD5") (pin "G16") (pinfunction "IO,_(DIFFIO_RX_R47p,_DIFFIOUT_R47p)_G16") (pintype "bidirectional"))
    )
    (net (code "129") (name "/QSPI_CLK") (class "Default")
      (node (ref "DD5") (pin "P15") (pinfunction "IO,_(DIFFIO_RX_R27n,_DIFFIOUT_R27n)_P15") (pintype "bidirectional"))
      (node (ref "U2") (pin "6") (pinfunction "CLK_6") (pintype "passive"))
    )
    (net (code "130") (name "/QSPI_CSN") (class "Default")
      (node (ref "DD5") (pin "M16") (pinfunction "IO,_(DIFFIO_RX_R33p,_DIFFIOUT_R33p)_M16") (pintype "bidirectional"))
      (node (ref "R21") (pin "1") (pinfunction "1_1") (pintype "passive"))
      (node (ref "U2") (pin "1") (pinfunction "~{CS}_1") (pintype "passive"))
    )
    (net (code "131") (name "/QSPI_D0") (class "Default")
      (node (ref "DD5") (pin "R16") (pinfunction "IO,_VREFB5N0_R16") (pintype "bidirectional"))
      (node (ref "U2") (pin "5") (pinfunction "DQ0_5") (pintype "passive"))
    )
    (net (code "132") (name "/QSPI_D1") (class "Default")
      (node (ref "DD5") (pin "M15") (pinfunction "IO,_(DIFFIO_RX_R28p,_DIFFIOUT_R28p)_M15") (pintype "bidirectional"))
      (node (ref "U2") (pin "2") (pinfunction "DQ1(DO)_2") (pintype "passive"))
    )
    (net (code "133") (name "/QSPI_D2") (class "Default")
      (node (ref "DD5") (pin "N16") (pinfunction "IO,_(DIFFIO_RX_R29p,_DIFFIOUT_R29p)_N16") (pintype "bidirectional"))
      (node (ref "U2") (pin "3") (pinfunction "DQ2(~{WP})_3") (pintype "passive"))
    )
    (net (code "134") (name "/QSPI_D3") (class "Default")
      (node (ref "DD5") (pin "P16") (pinfunction "IO,_(DIFFIO_RX_R29n,_DIFFIOUT_R29n)_P16") (pintype "bidirectional"))
      (node (ref "U2") (pin "7") (pinfunction "DQ3(~{HOLD})_7") (pintype "passive"))
    )
    (net (code "135") (name "/R0") (class "Default")
      (node (ref "DD5") (pin "T4") (pinfunction "IO,_(DIFFIO_RX_B14p,_DIFFIOUT_B14p)_T4") (pintype "bidirectional"))
    )
    (net (code "136") (name "/R1") (class "Default")
      (node (ref "DD5") (pin "R4") (pinfunction "IO,_(DIFFIO_TX_RX_B5n,_DIFFIOUT_B5n)_R4") (pintype "bidirectional"))
    )
    (net (code "137") (name "/R2") (class "Default")
      (node (ref "DD5") (pin "T3") (pinfunction "IO,_(DIFFIO_RX_B6n,_DIFFIOUT_B6n)_T3") (pintype "bidirectional"))
    )
    (net (code "138") (name "/R3") (class "Default")
      (node (ref "DD5") (pin "R3") (pinfunction "IO,_(DIFFIO_RX_B4n,_DIFFIOUT_B4n)_R3") (pintype "bidirectional"))
    )
    (net (code "139") (name "/R4") (class "Default")
      (node (ref "DD5") (pin "T2") (pinfunction "IO,_(DIFFIO_RX_B6p,_DIFFIOUT_B6p)_T2") (pintype "bidirectional"))
    )
    (net (code "140") (name "/R5") (class "Default")
      (node (ref "DD5") (pin "R2") (pinfunction "IO,_(DIFFIO_RX_B4p,_DIFFIOUT_B4p)_R2") (pintype "bidirectional"))
    )
    (net (code "141") (name "/R6") (class "Default")
      (node (ref "DD5") (pin "R1") (pinfunction "IO,_(DIFFIO_RX_B2p,_DIFFIOUT_B2p)_R1") (pintype "bidirectional"))
    )
    (net (code "142") (name "/R7") (class "Default")
      (node (ref "DD5") (pin "P2") (pinfunction "IO,_(DIFFIO_RX_B2n,_DIFFIOUT_B2n)_P2") (pintype "bidirectional"))
    )
    (net (code "143") (name "/RXD") (class "Default")
      (node (ref "DD5") (pin "L16") (pinfunction "IO,_(DIFFIO_RX_R33n,_DIFFIOUT_R33n)_L16") (pintype "bidirectional"))
    )
    (net (code "144") (name "/SCL") (class "Default")
      (node (ref "R26") (pin "1") (pinfunction "1_1") (pintype "passive"))
    )
    (net (code "145") (name "/SDA") (class "Default")
      (node (ref "R23") (pin "1") (pinfunction "1_1") (pintype "passive"))
    )
    (net (code "146") (name "/TXD") (class "Default")
      (node (ref "DD5") (pin "K15") (pinfunction "IO,_(DIFFIO_RX_R39n,_DIFFIOUT_R39n)_K15") (pintype "bidirectional"))
    )
    (net (code "147") (name "/VSYNC") (class "Default")
      (node (ref "DD5") (pin "N2") (pinfunction "IO,_DPCLK0,_(DIFFIO_RX_L38n,_DIFFIOUT_L38n)_N2") (pintype "bidirectional"))
    )
    (net (code "152") (name "3V3") (class "Default")
      (node (ref "C7") (pin "1") (pinfunction "1_1") (pintype "passive"))
      (node (ref "C90") (pin "2") (pinfunction "2_2") (pintype "passive"))
      (node (ref "C91") (pin "2") (pinfunction "2_2") (pintype "passive"))
      (node (ref "DD6") (pin "8") (pinfunction "Vcc_8") (pintype "power_in"))
      (node (ref "L3") (pin "1") (pinfunction "1_1") (pintype "passive"))
      (node (ref "R21") (pin "2") (pinfunction "2_2") (pintype "passive"))
      (node (ref "R22") (pin "1") (pinfunction "1_1") (pintype "passive"))
      (node (ref "R25") (pin "1") (pinfunction "1_1") (pintype "passive"))
      (node (ref "R27") (pin "1") (pinfunction "1_1") (pintype "passive"))
      (node (ref "R28") (pin "1") (pinfunction "1_1") (pintype "passive"))
      (node (ref "R32") (pin "1") (pinfunction "1_1") (pintype "passive"))
      (node (ref "R34") (pin "1") (pinfunction "1_1") (pintype "passive"))
      (node (ref "R56") (pin "1") (pinfunction "1_1") (pintype "passive"))
      (node (ref "R57") (pin "1") (pinfunction "1_1") (pintype "passive"))
      (node (ref "R58") (pin "1") (pinfunction "1_1") (pintype "passive"))
      (node (ref "R59") (pin "1") (pinfunction "1_1") (pintype "passive"))
      (node (ref "R6") (pin "2") (pinfunction "2_2") (pintype "passive"))
      (node (ref "R8") (pin "1") (pinfunction "1_1") (pintype "passive"))
      (node (ref "U2") (pin "8") (pinfunction "VCC_8") (pintype "passive"))
      (node (ref "U3") (pin "4") (pinfunction "Vcc_4") (pintype "power_in"))
      (node (ref "VD2") (pin "1") (pinfunction "1_1") (pintype "passive"))
      (node (ref "VD3") (pin "1") (pinfunction "1_1") (pintype "passive"))
      (node (ref "XP1") (pin "4") (pinfunction "4_4") (pintype "passive"))
    )
    (net (code "153") (name "GND") (class "Default")
      (node (ref "C30") (pin "1") (pinfunction "1_1") (pintype "passive"))
      (node (ref "C32") (pin "1") (pinfunction "1_1") (pintype "passive"))
      (node (ref "C7") (pin "2") (pinfunction "2_2") (pintype "passive"))
      (node (ref "C90") (pin "1") (pinfunction "1_1") (pintype "passive"))
      (node (ref "C91") (pin "1") (pinfunction "1_1") (pintype "passive"))
      (node (ref "DD6") (pin "1") (pinfunction "E0_1") (pintype "input"))
      (node (ref "DD6") (pin "2") (pinfunction "E1_2") (pintype "input"))
      (node (ref "DD6") (pin "3") (pinfunction "E2_3") (pintype "input"))
      (node (ref "DD6") (pin "4") (pinfunction "GND_4") (pintype "power_in"))
      (node (ref "DD6") (pin "7") (pinfunction "~{WC}_7") (pintype "input"))
      (node (ref "R29") (pin "2") (pinfunction "2_2") (pintype "passive"))
      (node (ref "R33") (pin "1") (pinfunction "1_1") (pintype "passive"))
      (node (ref "R52") (pin "2") (pinfunction "2_2") (pintype "passive"))
      (node (ref "R53") (pin "2") (pinfunction "2_2") (pintype "passive"))
      (node (ref "R54") (pin "2") (pinfunction "2_2") (pintype "passive"))
      (node (ref "R55") (pin "2") (pinfunction "2_2") (pintype "passive"))
      (node (ref "S1") (pin "2") (pinfunction "A2_2") (pintype "passive"))
      (node (ref "S1") (pin "4") (pinfunction "4_4") (pintype "passive"))
      (node (ref "U2") (pin "4") (pinfunction "VSS_4") (pintype "passive"))
      (node (ref "U3") (pin "1") (pinfunction "GND_1") (pintype "power_in"))
      (node (ref "XP1") (pin "10") (pinfunction "10_10") (pintype "passive"))
      (node (ref "XP1") (pin "2") (pinfunction "2_2") (pintype "passive"))
      (node (ref "Y1") (pin "2") (pinfunction "GND_2") (pintype "power_in"))
    )
    (net (code "154") (name "Net-(DD5B-JTAGEN)") (class "Default")
      (node (ref "DD5") (pin "G6") (pinfunction "JTAGEN_G6") (pintype "bidirectional"))
      (node (ref "R25") (pin "2") (pinfunction "2_2") (pintype "passive"))
    )
    (net (code "155") (name "Net-(DD5C-IO,_CLK1p,_(DIFFIO_RX_L36p,_DIFFIOUT_L36p))") (class "Default")
      (node (ref "C30") (pin "2") (pinfunction "2_2") (pintype "passive"))
      (node (ref "DD5") (pin "K6") (pinfunction "IO,_CLK1p,_(DIFFIO_RX_L36p,_DIFFIOUT_L36p)_K6") (pintype "bidirectional"))
      (node (ref "R7") (pin "2") (pinfunction "2_2") (pintype "passive"))
    )
    (net (code "156") (name "Net-(DD5C-IO,_PLL_L_CLKOUTn,_(DIFFIO_RX_L59n,_DIFFIOUT_L59n))") (class "Default")
      (node (ref "DD5") (pin "N3") (pinfunction "IO,_PLL_L_CLKOUTn,_(DIFFIO_RX_L59n,_DIFFIOUT_L59n)_N3") (pintype "bidirectional"))
      (node (ref "R9") (pin "2") (pinfunction "2_2") (pintype "passive"))
    )
    (net (code "157") (name "Net-(DD5F-IO,_(DIFFIO_RX_R2n,_DIFFIOUT_R2n))") (class "Default")
      (node (ref "DD5") (pin "T15") (pinfunction "IO,_(DIFFIO_RX_R2n,_DIFFIOUT_R2n)_T15") (pintype "bidirectional"))
      (node (ref "R23") (pin "2") (pinfunction "2_2") (pintype "passive"))
    )
    (net (code "158") (name "Net-(DD5F-IO,_RDN,_(DIFFIO_RX_R1n,_DIFFIOUT_R1n))") (class "Default")
      (node (ref "DD5") (pin "R14") (pinfunction "IO,_RDN,_(DIFFIO_RX_R1n,_DIFFIOUT_R1n)_R14") (pintype "bidirectional"))
      (node (ref "R26") (pin "2") (pinfunction "2_2") (pintype "passive"))
    )
    (net (code "159") (name "Net-(DD5I-IO,_CONFIG_SEL)") (class "Default")
      (node (ref "DD5") (pin "F8") (pinfunction "IO,_CONFIG_SEL_F8") (pintype "bidirectional"))
      (node (ref "R33") (pin "2") (pinfunction "2_2") (pintype "passive"))
    )
    (net (code "160") (name "Net-(DD5I-IO,_CONF_DONE,_(DIFFIO_RX_T50n,_DIFFIOUT_T50n))") (class "Default")
      (node (ref "DD5") (pin "E7") (pinfunction "IO,_CONF_DONE,_(DIFFIO_RX_T50n,_DIFFIOUT_T50n)_E7") (pintype "bidirectional"))
      (node (ref "R32") (pin "2") (pinfunction "2_2") (pintype "passive"))
    )
    (net (code "161") (name "Net-(DD5I-IO,_nSTATUS,_(DIFFIO_RX_T50p,_DIFFIOUT_T50p))") (class "Default")
      (node (ref "DD5") (pin "F7") (pinfunction "IO,_nSTATUS,_(DIFFIO_RX_T50p,_DIFFIOUT_T50p)_F7") (pintype "bidirectional"))
      (node (ref "R34") (pin "2") (pinfunction "2_2") (pintype "passive"))
    )
    (net (code "162") (name "Net-(R5-Pad1)") (class "Default")
      (node (ref "R5") (pin "1") (pinfunction "1_1") (pintype "passive"))
      (node (ref "VD2") (pin "2") (pinfunction "2_2") (pintype "passive"))
    )
    (net (code "163") (name "Net-(R10-Pad1)") (class "Default")
      (node (ref "R10") (pin "1") (pinfunction "1_1") (pintype "passive"))
      (node (ref "VD3") (pin "2") (pinfunction "2_2") (pintype "passive"))
    )
    (net (code "164") (name "Net-(R56-Pad2)") (class "Default")
      (node (ref "R56") (pin "2") (pinfunction "2_2") (pintype "passive"))
      (node (ref "SW1") (pin "8") (pintype "passive"))
    )
    (net (code "165") (name "Net-(R57-Pad2)") (class "Default")
      (node (ref "R57") (pin "2") (pinfunction "2_2") (pintype "passive"))
      (node (ref "SW1") (pin "7") (pintype "passive"))
    )
    (net (code "166") (name "Net-(R58-Pad2)") (class "Default")
      (node (ref "R58") (pin "2") (pinfunction "2_2") (pintype "passive"))
      (node (ref "SW1") (pin "6") (pintype "passive"))
    )
    (net (code "167") (name "Net-(R59-Pad2)") (class "Default")
      (node (ref "R59") (pin "2") (pinfunction "2_2") (pintype "passive"))
      (node (ref "SW1") (pin "5") (pintype "passive"))
    )
    (net (code "168") (name "Net-(S1-A1)") (class "Default")
      (node (ref "S1") (pin "1") (pinfunction "A1_1") (pintype "passive"))
      (node (ref "S1") (pin "3") (pinfunction "A3_3") (pintype "passive"))
      (node (ref "U3") (pin "3") (pinfunction "~{MR}_3") (pintype "passive"))
    )
    (net (code "169") (name "Net-(Y1-E{slash}D)") (class "Default")
      (node (ref "C32") (pin "2") (pinfunction "2_2") (pintype "passive"))
      (node (ref "L3") (pin "2") (pinfunction "2_2") (pintype "passive"))
      (node (ref "Y1") (pin "1") (pinfunction "E/D_1") (pintype "input"))
      (node (ref "Y1") (pin "4") (pinfunction "VCC_4") (pintype "power_in"))
    )
    (net (code "170") (name "unconnected-(DD5A-IO,_(DIFFIO_RX_L1n,_DIFFIOUT_L1n)-PadF5)") (class "Default")
      (node (ref "DD5") (pin "F5") (pinfunction "IO,_(DIFFIO_RX_L1n,_DIFFIOUT_L1n)_F5") (pintype "bidirectional"))
    )
    (net (code "171") (name "unconnected-(DD5A-IO,_(DIFFIO_RX_L3n,_DIFFIOUT_L3n)-PadH5)") (class "Default")
      (node (ref "DD5") (pin "H5") (pinfunction "IO,_(DIFFIO_RX_L3n,_DIFFIOUT_L3n)_H5") (pintype "bidirectional"))
    )
    (net (code "172") (name "unconnected-(DD5A-IO,_(DIFFIO_RX_L3p,_DIFFIOUT_L3p)-PadG5)") (class "Default")
      (node (ref "DD5") (pin "G5") (pinfunction "IO,_(DIFFIO_RX_L3p,_DIFFIOUT_L3p)_G5") (pintype "bidirectional"))
    )
    (net (code "173") (name "unconnected-(DD5B-IO,_(DIFFIO_RX_L20n,_DIFFIOUT_L20n)-PadJ5)") (class "Default")
      (node (ref "DD5") (pin "J5") (pinfunction "IO,_(DIFFIO_RX_L20n,_DIFFIOUT_L20n)_J5") (pintype "bidirectional"))
    )
    (net (code "174") (name "unconnected-(DD5B-IO,_(DIFFIO_RX_L20p,_DIFFIOUT_L20p)-PadH6)") (class "Default")
      (node (ref "DD5") (pin "H6") (pinfunction "IO,_(DIFFIO_RX_L20p,_DIFFIOUT_L20p)_H6") (pintype "bidirectional"))
    )
    (net (code "175") (name "unconnected-(DD5B-IO,_(DIFFIO_RX_L22n,_DIFFIOUT_L22n)-PadJ3)") (class "Default")
      (node (ref "DD5") (pin "J3") (pinfunction "IO,_(DIFFIO_RX_L22n,_DIFFIOUT_L22n)_J3") (pintype "bidirectional"))
    )
    (net (code "176") (name "unconnected-(DD5B-VREFB1N0-PadJ1)") (class "Default")
      (node (ref "DD5") (pin "J1") (pinfunction "VREFB1N0_J1") (pintype "bidirectional"))
    )
    (net (code "177") (name "unconnected-(DD5C-IO,_(DIFFIO_RX_L37n,_DIFFIOUT_L37n)-PadM2)") (class "Default")
      (node (ref "DD5") (pin "M2") (pinfunction "IO,_(DIFFIO_RX_L37n,_DIFFIOUT_L37n)_M2") (pintype "bidirectional"))
    )
    (net (code "178") (name "unconnected-(DD5C-IO,_(DIFFIO_RX_L41n,_DIFFIOUT_L41n)-PadK5)") (class "Default")
      (node (ref "DD5") (pin "K5") (pinfunction "IO,_(DIFFIO_RX_L41n,_DIFFIOUT_L41n)_K5") (pintype "bidirectional"))
    )
    (net (code "179") (name "unconnected-(DD5C-IO,_(DIFFIO_RX_L41p,_DIFFIOUT_L41p)-PadL6)") (class "Default")
      (node (ref "DD5") (pin "L6") (pinfunction "IO,_(DIFFIO_RX_L41p,_DIFFIOUT_L41p)_L6") (pintype "bidirectional"))
    )
    (net (code "180") (name "unconnected-(DD5C-IO,_CLK0n,_(DIFFIO_RX_L28n,_DIFFIOUT_L28n)-PadM3)") (class "Default")
      (node (ref "DD5") (pin "M3") (pinfunction "IO,_CLK0n,_(DIFFIO_RX_L28n,_DIFFIOUT_L28n)_M3") (pintype "bidirectional"))
    )
    (net (code "181") (name "unconnected-(DD5C-IO,_CLK1n,_(DIFFIO_RX_L36n,_DIFFIOUT_L36n)-PadJ6)") (class "Default")
      (node (ref "DD5") (pin "J6") (pinfunction "IO,_CLK1n,_(DIFFIO_RX_L36n,_DIFFIOUT_L36n)_J6") (pintype "bidirectional"))
    )
    (net (code "182") (name "unconnected-(DD5C-VREFB2N0-PadM1)") (class "Default")
      (node (ref "DD5") (pin "M1") (pinfunction "VREFB2N0_M1") (pintype "bidirectional"))
    )
    (net (code "183") (name "unconnected-(DD5D-IO,_(DIFFIO_TX_RX_B3n,_DIFFIOUT_B3n)-PadM6)") (class "Default")
      (node (ref "DD5") (pin "M6") (pinfunction "IO,_(DIFFIO_TX_RX_B3n,_DIFFIOUT_B3n)_M6") (pintype "bidirectional"))
    )
    (net (code "184") (name "unconnected-(DD5D-IO,_(DIFFIO_TX_RX_B3p,_DIFFIOUT_B3p)-PadL7)") (class "Default")
      (node (ref "DD5") (pin "L7") (pinfunction "IO,_(DIFFIO_TX_RX_B3p,_DIFFIOUT_B3p)_L7") (pintype "bidirectional"))
    )
    (net (code "185") (name "unconnected-(DD5D-IO,_(DIFFIO_TX_RX_B15n,_DIFFIOUT_B15n)-PadM7)") (class "Default")
      (node (ref "DD5") (pin "M7") (pinfunction "IO,_(DIFFIO_TX_RX_B15n,_DIFFIOUT_B15n)_M7") (pintype "bidirectional"))
    )
    (net (code "186") (name "unconnected-(DD5D-IO,_(DIFFIO_TX_RX_B15p,_DIFFIOUT_B15p)-PadL8)") (class "Default")
      (node (ref "DD5") (pin "L8") (pinfunction "IO,_(DIFFIO_TX_RX_B15p,_DIFFIOUT_B15p)_L8") (pintype "bidirectional"))
    )
    (net (code "187") (name "unconnected-(DD5D-IO,_CLK7n,_(DIFFIO_TX_RX_B20n,_DIFFIOUT_B20n)-PadM8)") (class "Default")
      (node (ref "DD5") (pin "M8") (pinfunction "IO,_CLK7n,_(DIFFIO_TX_RX_B20n,_DIFFIOUT_B20n)_M8") (pintype "bidirectional"))
    )
    (net (code "188") (name "unconnected-(DD5D-IO,_CLK7p,_(DIFFIO_TX_RX_B20p,_DIFFIOUT_B20p)-PadM9)") (class "Default")
      (node (ref "DD5") (pin "M9") (pinfunction "IO,_CLK7p,_(DIFFIO_TX_RX_B20p,_DIFFIOUT_B20p)_M9") (pintype "bidirectional"))
    )
    (net (code "189") (name "unconnected-(DD5E-IO,_(DIFFIO_TX_RX_B36n,_DIFFIOUT_B36n)-PadM10)") (class "Default")
      (node (ref "DD5") (pin "M10") (pinfunction "IO,_(DIFFIO_TX_RX_B36n,_DIFFIOUT_B36n)_M10") (pintype "bidirectional"))
    )
    (net (code "190") (name "unconnected-(DD5E-IO,_(DIFFIO_TX_RX_B36p,_DIFFIOUT_B36p)-PadL9)") (class "Default")
      (node (ref "DD5") (pin "L9") (pinfunction "IO,_(DIFFIO_TX_RX_B36p,_DIFFIOUT_B36p)_L9") (pintype "bidirectional"))
    )
    (net (code "191") (name "unconnected-(DD5E-IO,_PLL_B_CLKOUTn,_(DIFFIO_TX_RX_B57n,_DIFFIOUT_B57n)-PadM11)") (class "Default")
      (node (ref "DD5") (pin "M11") (pinfunction "IO,_PLL_B_CLKOUTn,_(DIFFIO_TX_RX_B57n,_DIFFIOUT_B57n)_M11") (pintype "bidirectional"))
    )
    (net (code "192") (name "unconnected-(DD5E-IO,_PLL_B_CLKOUTp,_(DIFFIO_TX_RX_B57p,_DIFFIOUT_B57p)-PadL10)") (class "Default")
      (node (ref "DD5") (pin "L10") (pinfunction "IO,_PLL_B_CLKOUTp,_(DIFFIO_TX_RX_B57p,_DIFFIOUT_B57p)_L10") (pintype "bidirectional"))
    )
    (net (code "193") (name "unconnected-(DD5F-IO,_(DIFFIO_RX_R25n,_DIFFIOUT_R25n)-PadL12)") (class "Default")
      (node (ref "DD5") (pin "L12") (pinfunction "IO,_(DIFFIO_RX_R25n,_DIFFIOUT_R25n)_L12") (pintype "bidirectional"))
    )
    (net (code "194") (name "unconnected-(DD5F-IO,_(DIFFIO_RX_R25p,_DIFFIOUT_R25p)-PadL11)") (class "Default")
      (node (ref "DD5") (pin "L11") (pinfunction "IO,_(DIFFIO_RX_R25p,_DIFFIOUT_R25p)_L11") (pintype "bidirectional"))
    )
    (net (code "195") (name "unconnected-(DD5F-IO,_(DIFFIO_RX_R28n,_DIFFIOUT_R28n)-PadM14)") (class "Default")
      (node (ref "DD5") (pin "M14") (pinfunction "IO,_(DIFFIO_RX_R28n,_DIFFIOUT_R28n)_M14") (pintype "bidirectional"))
    )
    (net (code "196") (name "unconnected-(DD5F-IO,_(DIFFIO_RX_R30n,_DIFFIOUT_R30n)-PadK12)") (class "Default")
      (node (ref "DD5") (pin "K12") (pinfunction "IO,_(DIFFIO_RX_R30n,_DIFFIOUT_R30n)_K12") (pintype "bidirectional"))
    )
    (net (code "197") (name "unconnected-(DD5F-IO,_(DIFFIO_RX_R30p,_DIFFIOUT_R30p)-PadK11)") (class "Default")
      (node (ref "DD5") (pin "K11") (pinfunction "IO,_(DIFFIO_RX_R30p,_DIFFIOUT_R30p)_K11") (pintype "bidirectional"))
    )
    (net (code "198") (name "unconnected-(DD5F-IO,_(DIFFIO_RX_R32p,_DIFFIOUT_R32p)-PadK14)") (class "Default")
      (node (ref "DD5") (pin "K14") (pinfunction "IO,_(DIFFIO_RX_R32p,_DIFFIOUT_R32p)_K14") (pintype "bidirectional"))
    )
    (net (code "199") (name "unconnected-(DD5G-IO,_(DIFFIO_RX_R39p,_DIFFIOUT_R39p)-PadJ14)") (class "Default")
      (node (ref "DD5") (pin "J14") (pinfunction "IO,_(DIFFIO_RX_R39p,_DIFFIOUT_R39p)_J14") (pintype "bidirectional"))
    )
    (net (code "200") (name "unconnected-(DD5G-IO,_(DIFFIO_RX_R44n,_DIFFIOUT_R44n)-PadH12)") (class "Default")
      (node (ref "DD5") (pin "H12") (pinfunction "IO,_(DIFFIO_RX_R44n,_DIFFIOUT_R44n)_H12") (pintype "bidirectional"))
    )
    (net (code "201") (name "unconnected-(DD5G-IO,_(DIFFIO_RX_R44p,_DIFFIOUT_R44p)-PadH11)") (class "Default")
      (node (ref "DD5") (pin "H11") (pinfunction "IO,_(DIFFIO_RX_R44p,_DIFFIOUT_R44p)_H11") (pintype "bidirectional"))
    )
    (net (code "202") (name "unconnected-(DD5G-IO,_(DIFFIO_RX_R51n,_DIFFIOUT_R51n)-PadE14)") (class "Default")
      (node (ref "DD5") (pin "E14") (pinfunction "IO,_(DIFFIO_RX_R51n,_DIFFIOUT_R51n)_E14") (pintype "bidirectional"))
    )
    (net (code "203") (name "unconnected-(DD5G-IO,_CLK2n,_(DIFFIO_RX_R38n,_DIFFIOUT_R38n)-PadJ12)") (class "Default")
      (node (ref "DD5") (pin "J12") (pinfunction "IO,_CLK2n,_(DIFFIO_RX_R38n,_DIFFIOUT_R38n)_J12") (pintype "bidirectional"))
    )
    (net (code "204") (name "unconnected-(DD5G-IO,_CLK2p,_(DIFFIO_RX_R38p,_DIFFIOUT_R38p)-PadJ11)") (class "Default")
      (node (ref "DD5") (pin "J11") (pinfunction "IO,_CLK2p,_(DIFFIO_RX_R38p,_DIFFIOUT_R38p)_J11") (pintype "bidirectional"))
    )
    (net (code "205") (name "unconnected-(DD5G-IO,_DPCLK2,_(DIFFIO_RX_R50n,_DIFFIOUT_R50n)-PadG12)") (class "Default")
      (node (ref "DD5") (pin "G12") (pinfunction "IO,_DPCLK2,_(DIFFIO_RX_R50n,_DIFFIOUT_R50n)_G12") (pintype "bidirectional"))
    )
    (net (code "206") (name "unconnected-(DD5G-IO,_DPCLK3,_(DIFFIO_RX_R50p,_DIFFIOUT_R50p)-PadG11)") (class "Default")
      (node (ref "DD5") (pin "G11") (pinfunction "IO,_DPCLK3,_(DIFFIO_RX_R50p,_DIFFIOUT_R50p)_G11") (pintype "bidirectional"))
    )
    (net (code "207") (name "unconnected-(DD5G-IO,_PLL_R_CLKOUTp,_(DIFFIO_RX_R69p,_DIFFIOUT_R69p)-PadD14)") (class "Default")
      (node (ref "DD5") (pin "D14") (pinfunction "IO,_PLL_R_CLKOUTp,_(DIFFIO_RX_R69p,_DIFFIOUT_R69p)_D14") (pintype "bidirectional"))
    )
    (net (code "208") (name "unconnected-(DD5H-IO,_(DIFFIO_RX_T1n,_DIFFIOUT_T1n)-PadE11)") (class "Default")
      (node (ref "DD5") (pin "E11") (pinfunction "IO,_(DIFFIO_RX_T1n,_DIFFIOUT_T1n)_E11") (pintype "bidirectional"))
    )
    (net (code "209") (name "unconnected-(DD5H-IO,_(DIFFIO_RX_T1p,_DIFFIOUT_T1p)-PadD12)") (class "Default")
      (node (ref "DD5") (pin "D12") (pinfunction "IO,_(DIFFIO_RX_T1p,_DIFFIOUT_T1p)_D12") (pintype "bidirectional"))
    )
    (net (code "210") (name "unconnected-(DD5H-IO,_(DIFFIO_RX_T2n,_DIFFIOUT_T2n)-PadC12)") (class "Default")
      (node (ref "DD5") (pin "C12") (pinfunction "IO,_(DIFFIO_RX_T2n,_DIFFIOUT_T2n)_C12") (pintype "bidirectional"))
    )
    (net (code "211") (name "unconnected-(DD5H-IO,_(DIFFIO_RX_T2p,_DIFFIOUT_T2p)-PadC13)") (class "Default")
      (node (ref "DD5") (pin "C13") (pinfunction "IO,_(DIFFIO_RX_T2p,_DIFFIOUT_T2p)_C13") (pintype "bidirectional"))
    )
    (net (code "212") (name "unconnected-(DD5H-IO,_(DIFFIO_RX_T17n,_DIFFIOUT_T17n)-PadF12)") (class "Default")
      (node (ref "DD5") (pin "F12") (pinfunction "IO,_(DIFFIO_RX_T17n,_DIFFIOUT_T17n)_F12") (pintype "bidirectional"))
    )
    (net (code "213") (name "unconnected-(DD5H-IO,_(DIFFIO_RX_T17p,_DIFFIOUT_T17p)-PadF11)") (class "Default")
      (node (ref "DD5") (pin "F11") (pinfunction "IO,_(DIFFIO_RX_T17p,_DIFFIOUT_T17p)_F11") (pintype "bidirectional"))
    )
    (net (code "214") (name "unconnected-(DD5H-IO,_(DIFFIO_RX_T28p,_DIFFIOUT_T28p)-PadF10)") (class "Default")
      (node (ref "DD5") (pin "F10") (pinfunction "IO,_(DIFFIO_RX_T28p,_DIFFIOUT_T28p)_F10") (pintype "bidirectional"))
    )
    (net (code "215") (name "unconnected-(DD5H-VREFB7N0-PadA15)") (class "Default")
      (node (ref "DD5") (pin "A15") (pinfunction "VREFB7N0_A15") (pintype "bidirectional"))
    )
    (net (code "216") (name "unconnected-(DD5I-IO,_(DIFFIO_RX_T42p,_DIFFIOUT_T42p)-PadC10)") (class "Default")
      (node (ref "DD5") (pin "C10") (pinfunction "IO,_(DIFFIO_RX_T42p,_DIFFIOUT_T42p)_C10") (pintype "bidirectional"))
    )
    (net (code "217") (name "unconnected-(DD5I-IO,_CLK4n,_(DIFFIO_RX_T38n,_DIFFIOUT_T38n)-PadC9)") (class "Default")
      (node (ref "DD5") (pin "C9") (pinfunction "IO,_CLK4n,_(DIFFIO_RX_T38n,_DIFFIOUT_T38n)_C9") (pintype "bidirectional"))
    )
    (net (code "218") (name "unconnected-(DD5I-IO,_CLK5p,_(DIFFIO_RX_T40p,_DIFFIOUT_T40p)-PadF9)") (class "Default")
      (node (ref "DD5") (pin "F9") (pinfunction "IO,_CLK5p,_(DIFFIO_RX_T40p,_DIFFIOUT_T40p)_F9") (pintype "bidirectional"))
    )
    (net (code "219") (name "unconnected-(XP1-Pad6)") (class "Default")
      (node (ref "XP1") (pin "6") (pinfunction "6_6") (pintype "passive+no_connect"))
    )
    (net (code "220") (name "unconnected-(XP1-Pad7)") (class "Default")
      (node (ref "XP1") (pin "7") (pinfunction "7_7") (pintype "passive+no_connect"))
    )
    (net (code "221") (name "unconnected-(XP1-Pad8)") (class "Default")
      (node (ref "XP1") (pin "8") (pinfunction "8_8") (pintype "passive+no_connect"))
    )
  )
)
